# sensors.net
KiCad netlist of a schematic drawn in Altium Designer
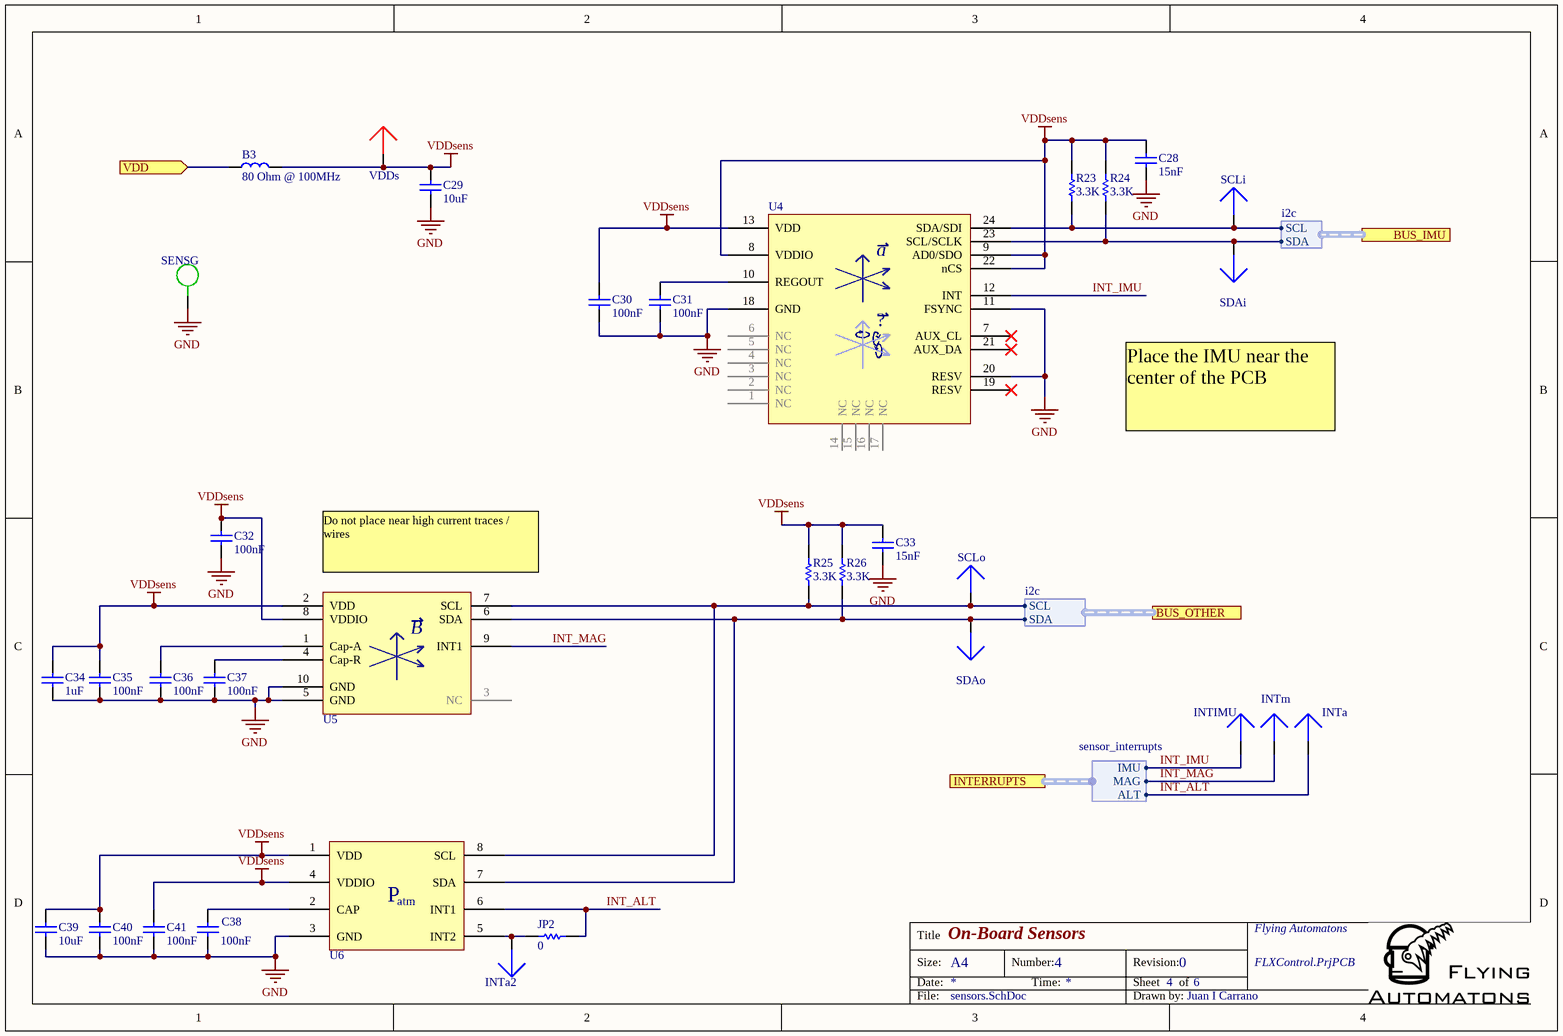
[diagram p0: sensors.SchDoc]

(export (version "E")
  (design (tool "Eeschema 10.0.6"))
  (components
    (comp (ref "B3")
      (value "80 Ohm @ 100MHz")
      (footprint "INDC1608L")
      (description "FERRITE CHIP 80 OHM 600MA 0603")
      (fields
        (field (name "MANUFACTURER") "Samsung Electro-Mechanics America, Inc")
        (field (name "MANUFACTURER PART NUMBER") "CIM10U800NC")
      )
      (libsource (lib "Passive#csv") (part "FERR_80/100M_0603_600m"))
    )
    (comp (ref "C28")
      (value "15nF")
      (footprint "CAPC1608L")
      (description "CAP CER 0.015UF 50V 10% X7R 0603")
      (fields (field (name "MANUFACTURER PART NUMBER") "CL10B153KB8SFNC"))
      (libsource (lib "Passive#csv") (part "CAP_15n_0603_50V_X7R_10%"))
    )
    (comp (ref "C29")
      (value "10uF")
      (footprint "CAPC3216L")
      (description "CAP CER 10UF 25V Y5V 1206")
      (fields (field (name "MANUFACTURER PART NUMBER") "TMK316F106ZL-T"))
      (libsource (lib "Passive#csv") (part "CAP_10u_1206_25V_Y5V"))
    )
    (comp (ref "C30")
      (value "100nF")
      (footprint "CAPC1608L")
      (description "CAP CER 0.1UF 50V Y5V 0603")
      (fields (field (name "MANUFACTURER PART NUMBER") "CC0603ZRY5V9BB104"))
      (libsource (lib "Passive#csv") (part "CAP_100n_0603_50V_Y5V"))
    )
    (comp (ref "C31")
      (value "100nF")
      (footprint "CAPC1608L")
      (description "CAP CER 0.1UF 50V Y5V 0603")
      (fields (field (name "MANUFACTURER PART NUMBER") "CC0603ZRY5V9BB104"))
      (libsource (lib "Passive#csv") (part "CAP_100n_0603_50V_Y5V"))
    )
    (comp (ref "C32")
      (value "100nF")
      (footprint "CAPC1608L")
      (description "CAP CER 0.1UF 50V Y5V 0603")
      (fields (field (name "MANUFACTURER PART NUMBER") "CC0603ZRY5V9BB104"))
      (libsource (lib "Passive#csv") (part "CAP_100n_0603_50V_Y5V"))
    )
    (comp (ref "C33")
      (value "15nF")
      (footprint "CAPC1608L")
      (description "CAP CER 0.015UF 50V 10% X7R 0603")
      (fields (field (name "MANUFACTURER PART NUMBER") "CL10B153KB8SFNC"))
      (libsource (lib "Passive#csv") (part "CAP_15n_0603_50V_X7R_10%"))
    )
    (comp (ref "C34")
      (value "1uF")
      (footprint "CAPC1608L")
      (description "CAP CER 1UF 25V 10% X5R 0603")
      (fields (field (name "MANUFACTURER PART NUMBER") "TMK107BJ105KA-T"))
      (libsource (lib "Passive#csv") (part "CAP_1u_0603_25V_X5R_10%"))
    )
    (comp (ref "C35")
      (value "100nF")
      (footprint "CAPC1608L")
      (description "CAP CER 0.1UF 50V Y5V 0603")
      (fields (field (name "MANUFACTURER PART NUMBER") "CC0603ZRY5V9BB104"))
      (libsource (lib "Passive#csv") (part "CAP_100n_0603_50V_Y5V"))
    )
    (comp (ref "C36")
      (value "100nF")
      (footprint "CAPC1608L")
      (description "CAP CER 0.1UF 50V Y5V 0603")
      (fields (field (name "MANUFACTURER PART NUMBER") "CC0603ZRY5V9BB104"))
      (libsource (lib "Passive#csv") (part "CAP_100n_0603_50V_Y5V"))
    )
    (comp (ref "C37")
      (value "100nF")
      (footprint "CAPC1608L")
      (description "CAP CER 0.1UF 50V Y5V 0603")
      (fields (field (name "MANUFACTURER PART NUMBER") "CC0603ZRY5V9BB104"))
      (libsource (lib "Passive#csv") (part "CAP_100n_0603_50V_Y5V"))
    )
    (comp (ref "C38")
      (value "100nF")
      (footprint "CAPC1608L")
      (description "CAP CER 0.1UF 50V Y5V 0603")
      (fields (field (name "MANUFACTURER PART NUMBER") "CC0603ZRY5V9BB104"))
      (libsource (lib "Passive#csv") (part "CAP_100n_0603_50V_Y5V"))
    )
    (comp (ref "C39")
      (value "10uF")
      (footprint "CAPC3216L")
      (description "CAP CER 10UF 25V Y5V 1206")
      (fields (field (name "MANUFACTURER PART NUMBER") "TMK316F106ZL-T"))
      (libsource (lib "Passive#csv") (part "CAP_10u_1206_25V_Y5V"))
    )
    (comp (ref "C40")
      (value "100nF")
      (footprint "CAPC1608L")
      (description "CAP CER 0.1UF 50V Y5V 0603")
      (fields (field (name "MANUFACTURER PART NUMBER") "CC0603ZRY5V9BB104"))
      (libsource (lib "Passive#csv") (part "CAP_100n_0603_50V_Y5V"))
    )
    (comp (ref "C41")
      (value "100nF")
      (footprint "CAPC1608L")
      (description "CAP CER 0.1UF 50V Y5V 0603")
      (fields (field (name "MANUFACTURER PART NUMBER") "CC0603ZRY5V9BB104"))
      (libsource (lib "Passive#csv") (part "CAP_100n_0603_50V_Y5V"))
    )
    (comp (ref "INTa")
      (value "TESTPOINT-ARROW-BLUE")
      (footprint "G-PIN_1mm-CIRCLE")
      (description "Tespoint")
      (libsource (lib "Connector#csv") (part "TESTP_SIG_1mm"))
    )
    (comp (ref "INTa2")
      (value "TESTPOINT-ARROW-BLUE")
      (footprint "G-PIN_1mm-CIRCLE")
      (description "Tespoint")
      (libsource (lib "Connector#csv") (part "TESTP_SIG_1mm"))
    )
    (comp (ref "INTIMU")
      (value "TESTPOINT-ARROW-BLUE")
      (footprint "G-PIN_1mm-CIRCLE")
      (description "Tespoint")
      (libsource (lib "Connector#csv") (part "TESTP_SIG_1mm"))
    )
    (comp (ref "INTm")
      (value "TESTPOINT-ARROW-BLUE")
      (footprint "G-PIN_1mm-CIRCLE")
      (description "Tespoint")
      (libsource (lib "Connector#csv") (part "TESTP_SIG_1mm"))
    )
    (comp (ref "JP2")
      (value "0")
      (footprint "RESC1608L")
      (description "RES 0.0 OHM 1/10W JUMP 0603")
      (fields (field (name "MANUFACTURER PART NUMBER") "RC1608J000CS"))
      (libsource (lib "Passive#csv") (part "RES_0_0603_0W1_1%"))
    )
    (comp (ref "R23")
      (value "3.3K")
      (footprint "RESC1608L")
      (description "RES 3.3K OHM 1/10W 1% 0603 SMD")
      (fields
        (field (name "MANUFACTURER") "Rohm Semiconductor")
        (field (name "MANUFACTURER PART NUMBER") "MCR03ERTF3301")
      )
      (libsource (lib "Passive#csv") (part "RES_3K3_0603_0W1_1%"))
    )
    (comp (ref "R24")
      (value "3.3K")
      (footprint "RESC1608L")
      (description "RES 3.3K OHM 1/10W 1% 0603 SMD")
      (fields
        (field (name "MANUFACTURER") "Rohm Semiconductor")
        (field (name "MANUFACTURER PART NUMBER") "MCR03ERTF3301")
      )
      (libsource (lib "Passive#csv") (part "RES_3K3_0603_0W1_1%"))
    )
    (comp (ref "R25")
      (value "3.3K")
      (footprint "RESC1608L")
      (description "RES 3.3K OHM 1/10W 1% 0603 SMD")
      (fields
        (field (name "MANUFACTURER") "Rohm Semiconductor")
        (field (name "MANUFACTURER PART NUMBER") "MCR03ERTF3301")
      )
      (libsource (lib "Passive#csv") (part "RES_3K3_0603_0W1_1%"))
    )
    (comp (ref "R26")
      (value "3.3K")
      (footprint "RESC1608L")
      (description "RES 3.3K OHM 1/10W 1% 0603 SMD")
      (fields
        (field (name "MANUFACTURER") "Rohm Semiconductor")
        (field (name "MANUFACTURER PART NUMBER") "MCR03ERTF3301")
      )
      (libsource (lib "Passive#csv") (part "RES_3K3_0603_0W1_1%"))
    )
    (comp (ref "SCLi")
      (value "TESTPOINT-ARROW-BLUE")
      (footprint "G-PIN_1mm-CIRCLE")
      (description "Tespoint")
      (libsource (lib "Connector#csv") (part "TESTP_SIG_1mm"))
    )
    (comp (ref "SCLo")
      (value "TESTPOINT-ARROW-BLUE")
      (footprint "G-PIN_1mm-CIRCLE")
      (description "Tespoint")
      (libsource (lib "Connector#csv") (part "TESTP_SIG_1mm"))
    )
    (comp (ref "SDAi")
      (value "TESTPOINT-ARROW-BLUE")
      (footprint "G-PIN_1mm-CIRCLE")
      (description "Tespoint")
      (libsource (lib "Connector#csv") (part "TESTP_SIG_1mm"))
    )
    (comp (ref "SDAo")
      (value "TESTPOINT-ARROW-BLUE")
      (footprint "G-PIN_1mm-CIRCLE")
      (description "Tespoint")
      (libsource (lib "Connector#csv") (part "TESTP_SIG_1mm"))
    )
    (comp (ref "SENSG")
      (value "TESTPOINT-CIRCLE-GREEN")
      (footprint "G-PIN_1mm-CROSS")
      (description "Ground Connection")
      (libsource (lib "Connector#csv") (part "TESTP_GND_GREEN_1mm"))
    )
    (comp (ref "U4")
      (value "MPU-6500")
      (footprint "QFN40P300X300X95-24N")
      (description "GYRO/ACCELEROMETER 6AXIS 24QFN")
      (fields (field (name "MANUFACTURER") "Invensense"))
      (libsource (lib "Mixed_Signal#csv") (part "MPU-6500"))
    )
    (comp (ref "U5")
      (value "MAG3110")
      (footprint "SON40P200X200X80-10WL")
      (description "XYZ Digital Magnetometer I2C")
      (fields
        (field (name "MANUFACTURER") "Freescale Semiconductor")
        (field (name "MANUFACTURER PART NUMBER") "MAG3110FCR1")
      )
      (libsource (lib "Mixed_Signal#csv") (part "MAG3110"))
    )
    (comp (ref "U6")
      (value "MPL3115A2")
      (footprint "x-FREE_2053-01(LGA8)")
      (description "IC ALTIMETER I2C VERSION 8LGA")
      (fields (field (name "MANUFACTURER") "Freescale Semiconductor"))
      (libsource (lib "Mixed_Signal#csv") (part "MPL3115A2"))
    )
    (comp (ref "VDDs")
      (value "TESTPOINT-ARROW-RED")
      (footprint "G-PIN_1mm-CIRCLE")
      (description "Tespoint for Power Trace")
      (libsource (lib "Connector#csv") (part "TESTP_PWR_1mm"))
    )
  )
  (nets
    (net (code "3") (name "/INT_ALT") (class "Default")
      (node (ref "INTa") (pin "1") (pinfunction "1_1") (pintype "passive"))
      (node (ref "JP2") (pin "1") (pinfunction "1_1") (pintype "passive"))
      (node (ref "U6") (pin "6") (pinfunction "INT1_6") (pintype "passive"))
    )
    (net (code "4") (name "/INT_IMU") (class "Default")
      (node (ref "INTIMU") (pin "1") (pinfunction "1_1") (pintype "passive"))
      (node (ref "U4") (pin "12") (pinfunction "INT_12") (pintype "passive"))
    )
    (net (code "5") (name "/INT_MAG") (class "Default")
      (node (ref "INTm") (pin "1") (pinfunction "1_1") (pintype "passive"))
      (node (ref "U5") (pin "9") (pinfunction "INT1_9") (pintype "passive"))
    )
    (net (code "6") (name "/VDD") (class "Default")
      (node (ref "B3") (pin "1") (pinfunction "1_1") (pintype "passive"))
    )
    (net (code "9") (name "GND") (class "Default")
      (node (ref "C28") (pin "2") (pinfunction "2_2") (pintype "passive"))
      (node (ref "C29") (pin "2") (pinfunction "2_2") (pintype "passive"))
      (node (ref "C30") (pin "2") (pinfunction "2_2") (pintype "passive"))
      (node (ref "C31") (pin "1") (pinfunction "1_1") (pintype "passive"))
      (node (ref "C32") (pin "2") (pinfunction "2_2") (pintype "passive"))
      (node (ref "C33") (pin "2") (pinfunction "2_2") (pintype "passive"))
      (node (ref "C34") (pin "2") (pinfunction "2_2") (pintype "passive"))
      (node (ref "C35") (pin "2") (pinfunction "2_2") (pintype "passive"))
      (node (ref "C36") (pin "2") (pinfunction "2_2") (pintype "passive"))
      (node (ref "C37") (pin "2") (pinfunction "2_2") (pintype "passive"))
      (node (ref "C38") (pin "2") (pinfunction "2_2") (pintype "passive"))
      (node (ref "C39") (pin "2") (pinfunction "2_2") (pintype "passive"))
      (node (ref "C40") (pin "2") (pinfunction "2_2") (pintype "passive"))
      (node (ref "C41") (pin "2") (pinfunction "2_2") (pintype "passive"))
      (node (ref "SENSG") (pin "1") (pinfunction "1_1") (pintype "passive"))
      (node (ref "U4") (pin "11") (pinfunction "FSYNC_11") (pintype "passive"))
      (node (ref "U4") (pin "18") (pinfunction "GND_18") (pintype "passive"))
      (node (ref "U4") (pin "20") (pinfunction "RESV_20") (pintype "passive"))
      (node (ref "U5") (pin "10") (pinfunction "GND_10") (pintype "passive"))
      (node (ref "U5") (pin "5") (pinfunction "GND_5") (pintype "passive"))
      (node (ref "U6") (pin "3") (pinfunction "GND_3") (pintype "passive"))
    )
    (net (code "10") (name "Net-(U4-REGOUT)") (class "Default")
      (node (ref "C31") (pin "2") (pinfunction "2_2") (pintype "passive"))
      (node (ref "U4") (pin "10") (pinfunction "REGOUT_10") (pintype "passive"))
    )
    (net (code "11") (name "Net-(U4-SCL{slash}SCLK)") (class "Default")
      (node (ref "R24") (pin "2") (pinfunction "2_2") (pintype "passive"))
      (node (ref "SDAi") (pin "1") (pinfunction "1_1") (pintype "passive"))
      (node (ref "U4") (pin "23") (pinfunction "SCL/SCLK_23") (pintype "passive"))
    )
    (net (code "12") (name "Net-(U4-SDA{slash}SDI)") (class "Default")
      (node (ref "R23") (pin "2") (pinfunction "2_2") (pintype "passive"))
      (node (ref "SCLi") (pin "1") (pinfunction "1_1") (pintype "passive"))
      (node (ref "U4") (pin "24") (pinfunction "SDA/SDI_24") (pintype "passive"))
    )
    (net (code "13") (name "Net-(U5-Cap-A)") (class "Default")
      (node (ref "C36") (pin "1") (pinfunction "1_1") (pintype "passive"))
      (node (ref "U5") (pin "1") (pinfunction "Cap-A_1") (pintype "passive"))
    )
    (net (code "14") (name "Net-(U5-Cap-R)") (class "Default")
      (node (ref "C37") (pin "1") (pinfunction "1_1") (pintype "passive"))
      (node (ref "U5") (pin "4") (pinfunction "Cap-R_4") (pintype "passive"))
    )
    (net (code "15") (name "Net-(U5-SCL)") (class "Default")
      (node (ref "R25") (pin "2") (pinfunction "2_2") (pintype "passive"))
      (node (ref "SCLo") (pin "1") (pinfunction "1_1") (pintype "passive"))
      (node (ref "U5") (pin "7") (pinfunction "SCL_7") (pintype "passive"))
      (node (ref "U6") (pin "8") (pinfunction "SCL_8") (pintype "passive"))
    )
    (net (code "16") (name "Net-(U5-SDA)") (class "Default")
      (node (ref "R26") (pin "2") (pinfunction "2_2") (pintype "passive"))
      (node (ref "SDAo") (pin "1") (pinfunction "1_1") (pintype "passive"))
      (node (ref "U5") (pin "6") (pinfunction "SDA_6") (pintype "passive"))
      (node (ref "U6") (pin "7") (pinfunction "SDA_7") (pintype "passive"))
    )
    (net (code "17") (name "Net-(U6-CAP)") (class "Default")
      (node (ref "C38") (pin "1") (pinfunction "1_1") (pintype "passive"))
      (node (ref "U6") (pin "2") (pinfunction "CAP_2") (pintype "passive"))
    )
    (net (code "18") (name "Net-(U6-INT2)") (class "Default")
      (node (ref "INTa2") (pin "1") (pinfunction "1_1") (pintype "passive"))
      (node (ref "JP2") (pin "2") (pinfunction "2_2") (pintype "passive"))
      (node (ref "U6") (pin "5") (pinfunction "INT2_5") (pintype "passive"))
    )
    (net (code "19") (name "VDDsens") (class "Default")
      (node (ref "B3") (pin "2") (pinfunction "2_2") (pintype "passive"))
      (node (ref "C28") (pin "1") (pinfunction "1_1") (pintype "passive"))
      (node (ref "C29") (pin "1") (pinfunction "1_1") (pintype "passive"))
      (node (ref "C30") (pin "1") (pinfunction "1_1") (pintype "passive"))
      (node (ref "C32") (pin "1") (pinfunction "1_1") (pintype "passive"))
      (node (ref "C33") (pin "1") (pinfunction "1_1") (pintype "passive"))
      (node (ref "C34") (pin "1") (pinfunction "1_1") (pintype "passive"))
      (node (ref "C35") (pin "1") (pinfunction "1_1") (pintype "passive"))
      (node (ref "C39") (pin "1") (pinfunction "1_1") (pintype "passive"))
      (node (ref "C40") (pin "1") (pinfunction "1_1") (pintype "passive"))
      (node (ref "C41") (pin "1") (pinfunction "1_1") (pintype "passive"))
      (node (ref "R23") (pin "1") (pinfunction "1_1") (pintype "passive"))
      (node (ref "R24") (pin "1") (pinfunction "1_1") (pintype "passive"))
      (node (ref "R25") (pin "1") (pinfunction "1_1") (pintype "passive"))
      (node (ref "R26") (pin "1") (pinfunction "1_1") (pintype "passive"))
      (node (ref "U4") (pin "13") (pinfunction "VDD_13") (pintype "passive"))
      (node (ref "U4") (pin "22") (pinfunction "nCS_22") (pintype "passive"))
      (node (ref "U4") (pin "8") (pinfunction "VDDIO_8") (pintype "passive"))
      (node (ref "U4") (pin "9") (pinfunction "AD0/SDO_9") (pintype "passive"))
      (node (ref "U5") (pin "2") (pinfunction "VDD_2") (pintype "passive"))
      (node (ref "U5") (pin "8") (pinfunction "VDDIO_8") (pintype "passive"))
      (node (ref "U6") (pin "1") (pinfunction "VDD_1") (pintype "passive"))
      (node (ref "U6") (pin "4") (pinfunction "VDDIO_4") (pintype "passive"))
      (node (ref "VDDs") (pin "1") (pinfunction "1_1") (pintype "passive"))
    )
    (net (code "20") (name "unconnected-(U4-AUX_CL-Pad7)") (class "Default")
      (node (ref "U4") (pin "7") (pinfunction "AUX_CL_7") (pintype "passive+no_connect"))
    )
    (net (code "21") (name "unconnected-(U4-AUX_DA-Pad21)") (class "Default")
      (node (ref "U4") (pin "21") (pinfunction "AUX_DA_21") (pintype "passive+no_connect"))
    )
    (net (code "22") (name "unconnected-(U4-NC-Pad1)") (class "Default")
      (node (ref "U4") (pin "1") (pinfunction "NC_1") (pintype "passive"))
    )
    (net (code "23") (name "unconnected-(U4-NC-Pad2)") (class "Default")
      (node (ref "U4") (pin "2") (pinfunction "NC_2") (pintype "passive"))
    )
    (net (code "24") (name "unconnected-(U4-NC-Pad3)") (class "Default")
      (node (ref "U4") (pin "3") (pinfunction "NC_3") (pintype "passive"))
    )
    (net (code "25") (name "unconnected-(U4-NC-Pad4)") (class "Default")
      (node (ref "U4") (pin "4") (pinfunction "NC_4") (pintype "passive"))
    )
    (net (code "26") (name "unconnected-(U4-NC-Pad5)") (class "Default")
      (node (ref "U4") (pin "5") (pinfunction "NC_5") (pintype "passive"))
    )
    (net (code "27") (name "unconnected-(U4-NC-Pad6)") (class "Default")
      (node (ref "U4") (pin "6") (pinfunction "NC_6") (pintype "passive"))
    )
    (net (code "28") (name "unconnected-(U4-NC-Pad14)") (class "Default")
      (node (ref "U4") (pin "14") (pinfunction "NC_14") (pintype "passive"))
    )
    (net (code "29") (name "unconnected-(U4-NC-Pad15)") (class "Default")
      (node (ref "U4") (pin "15") (pinfunction "NC_15") (pintype "passive"))
    )
    (net (code "30") (name "unconnected-(U4-NC-Pad16)") (class "Default")
      (node (ref "U4") (pin "16") (pinfunction "NC_16") (pintype "passive"))
    )
    (net (code "31") (name "unconnected-(U4-NC-Pad17)") (class "Default")
      (node (ref "U4") (pin "17") (pinfunction "NC_17") (pintype "passive"))
    )
    (net (code "32") (name "unconnected-(U4-RESV-Pad19)") (class "Default")
      (node (ref "U4") (pin "19") (pinfunction "RESV_19") (pintype "passive+no_connect"))
    )
    (net (code "33") (name "unconnected-(U5-NC-Pad3)") (class "Default")
      (node (ref "U5") (pin "3") (pinfunction "NC_3") (pintype "passive"))
    )
  )
)
